# version1c.net
KiCad netlist of a schematic drawn in EAGLE
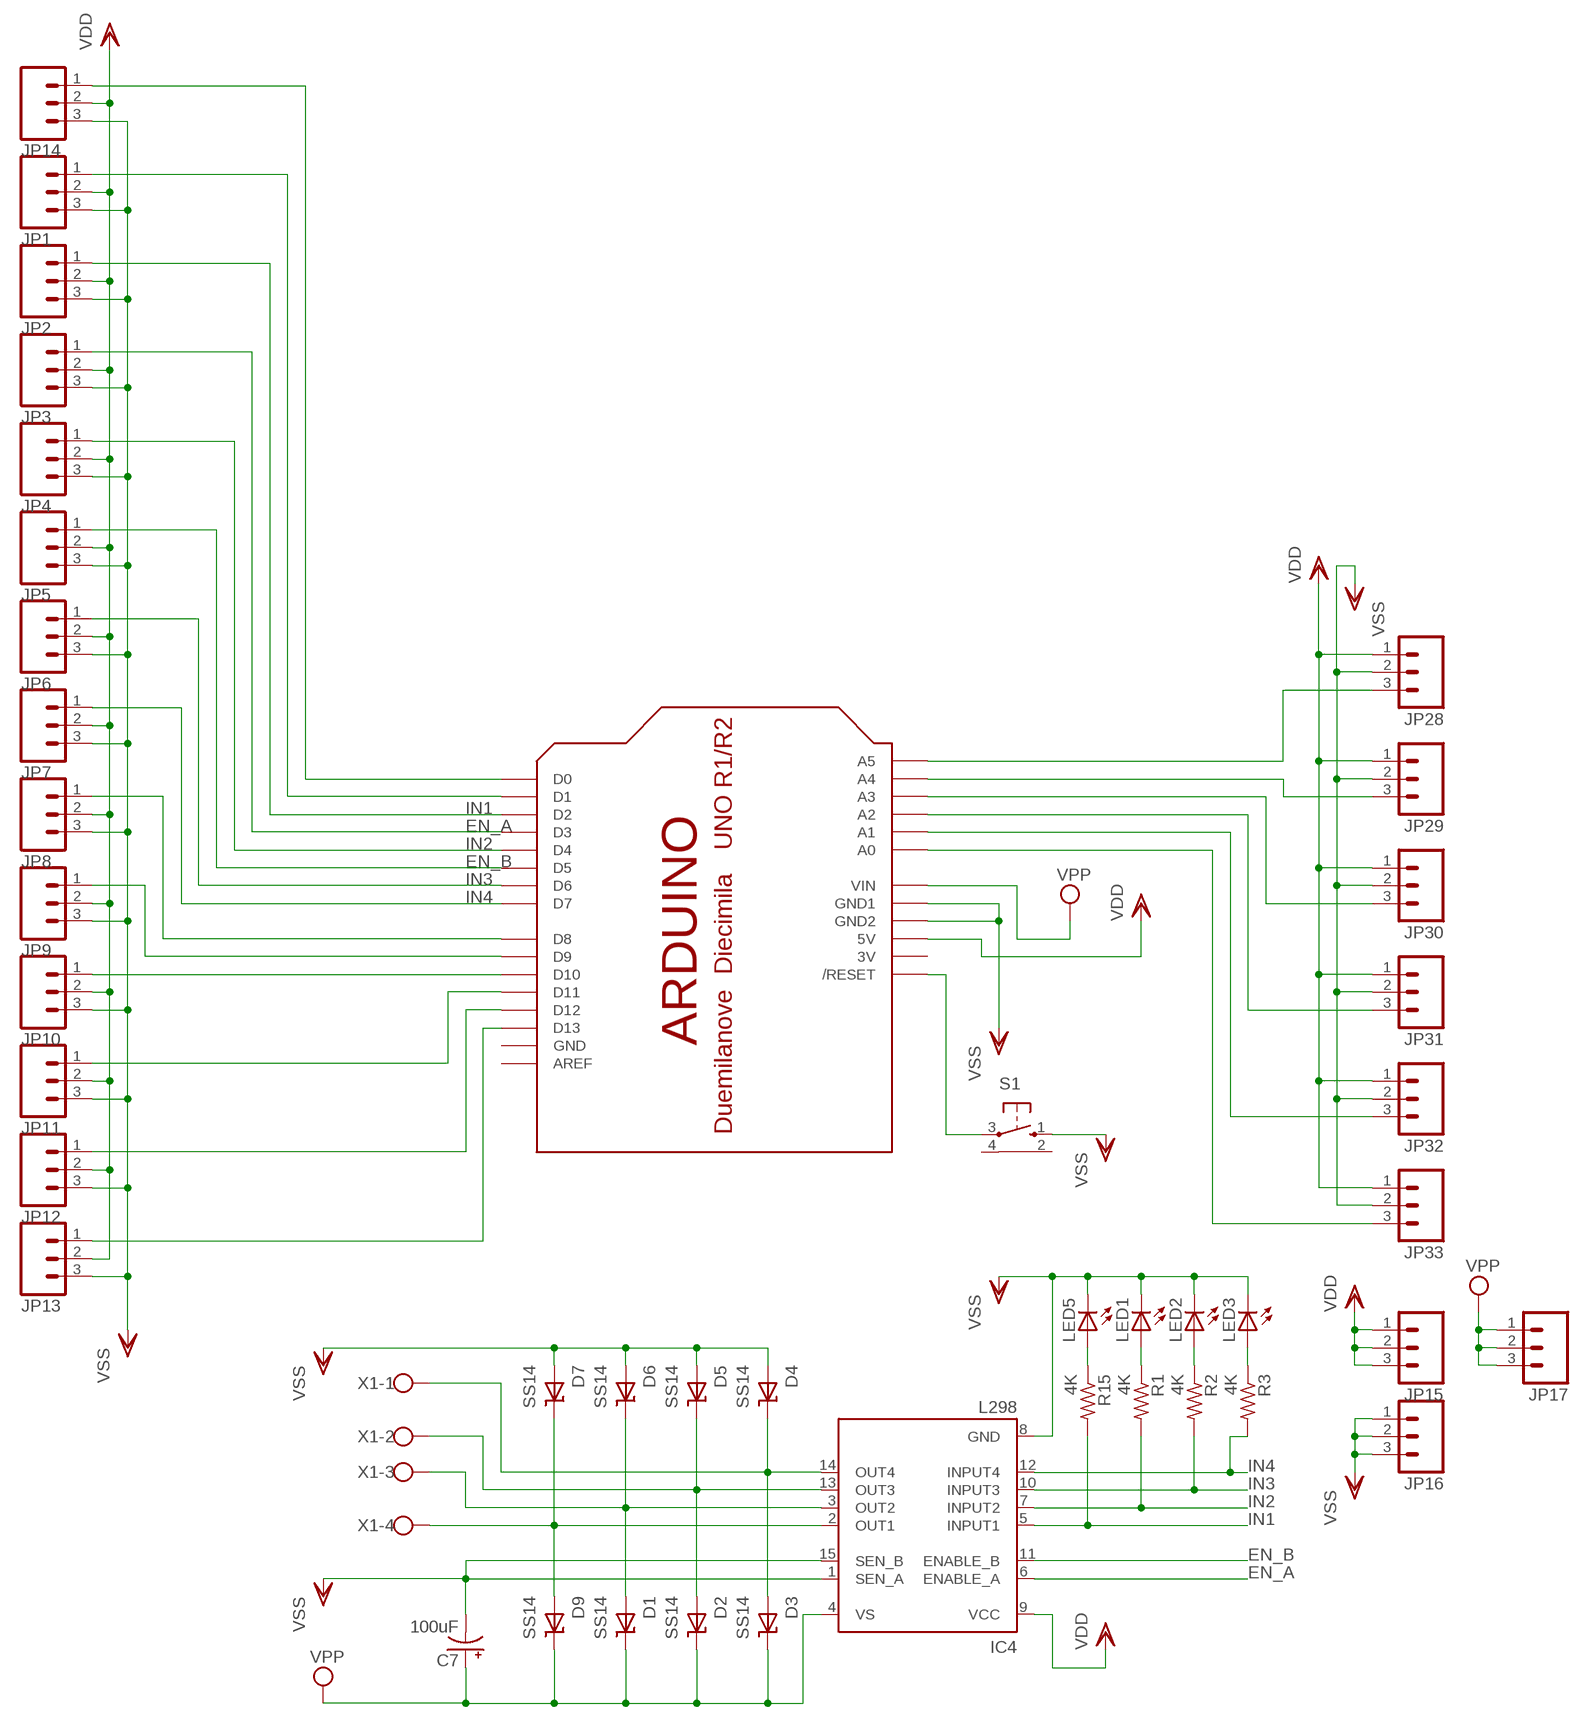
[diagram p0: schematic, sheet 1]

(export (version "E")
  (design (tool "Eeschema 10.0.6"))
  (components
    (comp (ref "C7")
      (value "100uF")
      (footprint "eagle-import:153CLV-0605")
      (libsource (lib "eagle-import") (part "CPOL-US153CLV-0605"))
    )
    (comp (ref "D1")
      (value "SS14")
      (footprint "eagle-import:SMA")
      (libsource (lib "eagle-import") (part "SS14"))
    )
    (comp (ref "D2")
      (value "SS14")
      (footprint "eagle-import:SMA")
      (libsource (lib "eagle-import") (part "SS14"))
    )
    (comp (ref "D3")
      (value "SS14")
      (footprint "eagle-import:SMA")
      (libsource (lib "eagle-import") (part "SS14"))
    )
    (comp (ref "D4")
      (value "SS14")
      (footprint "eagle-import:SMA")
      (libsource (lib "eagle-import") (part "SS14"))
    )
    (comp (ref "D5")
      (value "SS14")
      (footprint "eagle-import:SMA")
      (libsource (lib "eagle-import") (part "SS14"))
    )
    (comp (ref "D6")
      (value "SS14")
      (footprint "eagle-import:SMA")
      (libsource (lib "eagle-import") (part "SS14"))
    )
    (comp (ref "D7")
      (value "SS14")
      (footprint "eagle-import:SMA")
      (libsource (lib "eagle-import") (part "SS14"))
    )
    (comp (ref "D9")
      (value "SS14")
      (footprint "eagle-import:SMA")
      (libsource (lib "eagle-import") (part "SS14"))
    )
    (comp (ref "IC4")
      (value "L298")
      (footprint "eagle-import:MULTIWATT-15")
      (fields (field (name "MPN") "L298N"))
      (libsource (lib "eagle-import") (part "L298"))
    )
    (comp (ref "JP1")
      (value "M03PTH")
      (footprint "eagle-import:1X03")
      (libsource (lib "eagle-import") (part "M03PTH"))
    )
    (comp (ref "JP2")
      (value "M03PTH")
      (footprint "eagle-import:1X03")
      (libsource (lib "eagle-import") (part "M03PTH"))
    )
    (comp (ref "JP3")
      (value "M03PTH")
      (footprint "eagle-import:1X03")
      (libsource (lib "eagle-import") (part "M03PTH"))
    )
    (comp (ref "JP4")
      (value "M03PTH")
      (footprint "eagle-import:1X03")
      (libsource (lib "eagle-import") (part "M03PTH"))
    )
    (comp (ref "JP5")
      (value "M03PTH")
      (footprint "eagle-import:1X03")
      (libsource (lib "eagle-import") (part "M03PTH"))
    )
    (comp (ref "JP6")
      (value "M03PTH")
      (footprint "eagle-import:1X03")
      (libsource (lib "eagle-import") (part "M03PTH"))
    )
    (comp (ref "JP7")
      (value "M03PTH")
      (footprint "eagle-import:1X03")
      (libsource (lib "eagle-import") (part "M03PTH"))
    )
    (comp (ref "JP8")
      (value "M03PTH")
      (footprint "eagle-import:1X03")
      (libsource (lib "eagle-import") (part "M03PTH"))
    )
    (comp (ref "JP9")
      (value "M03PTH")
      (footprint "eagle-import:1X03")
      (libsource (lib "eagle-import") (part "M03PTH"))
    )
    (comp (ref "JP10")
      (value "M03PTH")
      (footprint "eagle-import:1X03")
      (libsource (lib "eagle-import") (part "M03PTH"))
    )
    (comp (ref "JP11")
      (value "M03PTH")
      (footprint "eagle-import:1X03")
      (libsource (lib "eagle-import") (part "M03PTH"))
    )
    (comp (ref "JP12")
      (value "M03PTH")
      (footprint "eagle-import:1X03")
      (libsource (lib "eagle-import") (part "M03PTH"))
    )
    (comp (ref "JP13")
      (value "M03PTH")
      (footprint "eagle-import:1X03")
      (libsource (lib "eagle-import") (part "M03PTH"))
    )
    (comp (ref "JP14")
      (value "M03PTH")
      (footprint "eagle-import:1X03")
      (libsource (lib "eagle-import") (part "M03PTH"))
    )
    (comp (ref "JP15")
      (value "M03PTH")
      (footprint "eagle-import:1X03")
      (libsource (lib "eagle-import") (part "M03PTH"))
    )
    (comp (ref "JP16")
      (value "M03PTH")
      (footprint "eagle-import:1X03")
      (libsource (lib "eagle-import") (part "M03PTH"))
    )
    (comp (ref "JP17")
      (value "M03PTH")
      (footprint "eagle-import:1X03")
      (libsource (lib "eagle-import") (part "M03PTH"))
    )
    (comp (ref "JP28")
      (value "M03PTH")
      (footprint "eagle-import:1X03")
      (libsource (lib "eagle-import") (part "M03PTH"))
    )
    (comp (ref "JP29")
      (value "M03PTH")
      (footprint "eagle-import:1X03")
      (libsource (lib "eagle-import") (part "M03PTH"))
    )
    (comp (ref "JP30")
      (value "M03PTH")
      (footprint "eagle-import:1X03")
      (libsource (lib "eagle-import") (part "M03PTH"))
    )
    (comp (ref "JP31")
      (value "M03PTH")
      (footprint "eagle-import:1X03")
      (libsource (lib "eagle-import") (part "M03PTH"))
    )
    (comp (ref "JP32")
      (value "M03PTH")
      (footprint "eagle-import:1X03")
      (libsource (lib "eagle-import") (part "M03PTH"))
    )
    (comp (ref "JP33")
      (value "M03PTH")
      (footprint "eagle-import:1X03")
      (libsource (lib "eagle-import") (part "M03PTH"))
    )
    (comp (ref "LED1")
      (value "LEDCHIP-LED0805")
      (footprint "eagle-import:CHIP-LED0805")
      (libsource (lib "eagle-import") (part "LEDCHIP-LED0805"))
    )
    (comp (ref "LED2")
      (value "LEDCHIP-LED0805")
      (footprint "eagle-import:CHIP-LED0805")
      (libsource (lib "eagle-import") (part "LEDCHIP-LED0805"))
    )
    (comp (ref "LED3")
      (value "LEDCHIP-LED0805")
      (footprint "eagle-import:CHIP-LED0805")
      (libsource (lib "eagle-import") (part "LEDCHIP-LED0805"))
    )
    (comp (ref "LED5")
      (value "LEDCHIP-LED0805")
      (footprint "eagle-import:CHIP-LED0805")
      (libsource (lib "eagle-import") (part "LEDCHIP-LED0805"))
    )
    (comp (ref "R1")
      (value "4K")
      (footprint "eagle-import:R0805")
      (libsource (lib "eagle-import") (part "R-US_R0805"))
    )
    (comp (ref "R2")
      (value "4K")
      (footprint "eagle-import:R0805")
      (libsource (lib "eagle-import") (part "R-US_R0805"))
    )
    (comp (ref "R3")
      (value "4K")
      (footprint "eagle-import:R0805")
      (libsource (lib "eagle-import") (part "R-US_R0805"))
    )
    (comp (ref "R15")
      (value "4K")
      (footprint "eagle-import:R0805")
      (libsource (lib "eagle-import") (part "R-US_R0805"))
    )
    (comp (ref "S1")
      (value "10-XX-RPAD")
      (footprint "eagle-import:B3F-10XX-RPAD")
      (libsource (lib "eagle-import") (part "10-XX-RPAD"))
    )
    (comp (ref "U$1")
      (value "ARDUINO-NOHOLE")
      (footprint "eagle-import:ARDUINO-NOHOLE")
      (libsource (lib "eagle-import") (part "ARDUINO-NOHOLE"))
    )
    (comp (ref "X1")
      (value "W237-4")
      (footprint "eagle-import:W237-4")
      (libsource (lib "eagle-import") (part "W237-4"))
    )
  )
  (nets
    (net (code "1") (name "/3V") (class "Default")
      (node (ref "U$1") (pin "3V") (pinfunction "3V_3V") (pintype "power_in"))
    )
    (net (code "2") (name "/EN_A") (class "Default")
      (node (ref "IC4") (pin "6") (pinfunction "ENABLE_A_6") (pintype "input"))
      (node (ref "JP3") (pin "1") (pinfunction "1_1") (pintype "passive"))
      (node (ref "U$1") (pin "D3") (pinfunction "D3_D3") (pintype "bidirectional"))
    )
    (net (code "3") (name "/EN_B") (class "Default")
      (node (ref "IC4") (pin "11") (pinfunction "ENABLE_B_11") (pintype "input"))
      (node (ref "JP5") (pin "1") (pinfunction "1_1") (pintype "passive"))
      (node (ref "U$1") (pin "D5") (pinfunction "D5_D5") (pintype "bidirectional"))
    )
    (net (code "4") (name "/GND") (class "Default")
      (node (ref "U$1") (pin "GND") (pinfunction "GND_GND") (pintype "power_in"))
    )
    (net (code "5") (name "/IN1") (class "Default")
      (node (ref "IC4") (pin "5") (pinfunction "INPUT1_5") (pintype "input"))
      (node (ref "JP2") (pin "1") (pinfunction "1_1") (pintype "passive"))
      (node (ref "R15") (pin "2") (pinfunction "2_2") (pintype "passive"))
      (node (ref "U$1") (pin "D2") (pinfunction "D2_D2") (pintype "bidirectional"))
    )
    (net (code "6") (name "/IN2") (class "Default")
      (node (ref "IC4") (pin "7") (pinfunction "INPUT2_7") (pintype "input"))
      (node (ref "JP4") (pin "1") (pinfunction "1_1") (pintype "passive"))
      (node (ref "R1") (pin "2") (pinfunction "2_2") (pintype "passive"))
      (node (ref "U$1") (pin "D4") (pinfunction "D4_D4") (pintype "bidirectional"))
    )
    (net (code "7") (name "/IN3") (class "Default")
      (node (ref "IC4") (pin "10") (pinfunction "INPUT3_10") (pintype "input"))
      (node (ref "JP6") (pin "1") (pinfunction "1_1") (pintype "passive"))
      (node (ref "R2") (pin "2") (pinfunction "2_2") (pintype "passive"))
      (node (ref "U$1") (pin "D6") (pinfunction "D6_D6") (pintype "bidirectional"))
    )
    (net (code "8") (name "/IN4") (class "Default")
      (node (ref "IC4") (pin "12") (pinfunction "INPUT4_12") (pintype "input"))
      (node (ref "JP7") (pin "1") (pinfunction "1_1") (pintype "passive"))
      (node (ref "R3") (pin "2") (pinfunction "2_2") (pintype "passive"))
      (node (ref "U$1") (pin "D7") (pinfunction "D7_D7") (pintype "bidirectional"))
    )
    (net (code "9") (name "Net-(D1-A)") (class "Default")
      (node (ref "D1") (pin "P$2") (pinfunction "A_P$2") (pintype "bidirectional"))
      (node (ref "D6") (pin "P$1") (pinfunction "K_P$1") (pintype "bidirectional"))
      (node (ref "IC4") (pin "3") (pinfunction "OUT2_3") (pintype "output"))
      (node (ref "X1") (pin "3") (pinfunction "KL_3") (pintype "passive"))
    )
    (net (code "10") (name "Net-(D2-A)") (class "Default")
      (node (ref "D2") (pin "P$2") (pinfunction "A_P$2") (pintype "bidirectional"))
      (node (ref "D5") (pin "P$1") (pinfunction "K_P$1") (pintype "bidirectional"))
      (node (ref "IC4") (pin "13") (pinfunction "OUT3_13") (pintype "output"))
      (node (ref "X1") (pin "2") (pinfunction "KL_2") (pintype "passive"))
    )
    (net (code "11") (name "Net-(D3-A)") (class "Default")
      (node (ref "D3") (pin "P$2") (pinfunction "A_P$2") (pintype "bidirectional"))
      (node (ref "D4") (pin "P$1") (pinfunction "K_P$1") (pintype "bidirectional"))
      (node (ref "IC4") (pin "14") (pinfunction "OUT4_14") (pintype "output"))
      (node (ref "X1") (pin "1") (pinfunction "KL_1") (pintype "passive"))
    )
    (net (code "12") (name "Net-(D7-K)") (class "Default")
      (node (ref "D7") (pin "P$1") (pinfunction "K_P$1") (pintype "bidirectional"))
      (node (ref "D9") (pin "P$2") (pinfunction "A_P$2") (pintype "bidirectional"))
      (node (ref "IC4") (pin "2") (pinfunction "OUT1_2") (pintype "output"))
      (node (ref "X1") (pin "4") (pinfunction "KL_4") (pintype "passive"))
    )
    (net (code "13") (name "Net-(JP1-Pad1)") (class "Default")
      (node (ref "JP1") (pin "1") (pinfunction "1_1") (pintype "passive"))
      (node (ref "U$1") (pin "D1") (pinfunction "D1_D1") (pintype "bidirectional"))
    )
    (net (code "14") (name "Net-(JP8-Pad1)") (class "Default")
      (node (ref "JP8") (pin "1") (pinfunction "1_1") (pintype "passive"))
      (node (ref "U$1") (pin "D8") (pinfunction "D8_D8") (pintype "bidirectional"))
    )
    (net (code "15") (name "Net-(JP9-Pad1)") (class "Default")
      (node (ref "JP9") (pin "1") (pinfunction "1_1") (pintype "passive"))
      (node (ref "U$1") (pin "D9") (pinfunction "D9_D9") (pintype "bidirectional"))
    )
    (net (code "16") (name "Net-(JP10-Pad1)") (class "Default")
      (node (ref "JP10") (pin "1") (pinfunction "1_1") (pintype "passive"))
      (node (ref "U$1") (pin "D10") (pinfunction "D10_D10") (pintype "bidirectional"))
    )
    (net (code "17") (name "Net-(JP11-Pad1)") (class "Default")
      (node (ref "JP11") (pin "1") (pinfunction "1_1") (pintype "passive"))
      (node (ref "U$1") (pin "D11") (pinfunction "D11_D11") (pintype "bidirectional"))
    )
    (net (code "18") (name "Net-(JP12-Pad1)") (class "Default")
      (node (ref "JP12") (pin "1") (pinfunction "1_1") (pintype "passive"))
      (node (ref "U$1") (pin "D12") (pinfunction "D12_D12") (pintype "bidirectional"))
    )
    (net (code "19") (name "Net-(JP13-Pad1)") (class "Default")
      (node (ref "JP13") (pin "1") (pinfunction "1_1") (pintype "passive"))
      (node (ref "U$1") (pin "D13") (pinfunction "D13_D13") (pintype "bidirectional"))
    )
    (net (code "20") (name "Net-(JP14-Pad1)") (class "Default")
      (node (ref "JP14") (pin "1") (pinfunction "1_1") (pintype "passive"))
      (node (ref "U$1") (pin "D0") (pinfunction "D0_D0") (pintype "bidirectional"))
    )
    (net (code "21") (name "Net-(JP28-Pad3)") (class "Default")
      (node (ref "JP28") (pin "3") (pinfunction "3_3") (pintype "passive"))
      (node (ref "U$1") (pin "A5") (pinfunction "A5_A5") (pintype "bidirectional"))
    )
    (net (code "22") (name "Net-(JP29-Pad3)") (class "Default")
      (node (ref "JP29") (pin "3") (pinfunction "3_3") (pintype "passive"))
      (node (ref "U$1") (pin "A4") (pinfunction "A4_A4") (pintype "bidirectional"))
    )
    (net (code "23") (name "Net-(JP30-Pad3)") (class "Default")
      (node (ref "JP30") (pin "3") (pinfunction "3_3") (pintype "passive"))
      (node (ref "U$1") (pin "A3") (pinfunction "A3_A3") (pintype "bidirectional"))
    )
    (net (code "24") (name "Net-(JP31-Pad3)") (class "Default")
      (node (ref "JP31") (pin "3") (pinfunction "3_3") (pintype "passive"))
      (node (ref "U$1") (pin "A2") (pinfunction "A2_A2") (pintype "bidirectional"))
    )
    (net (code "25") (name "Net-(JP32-Pad3)") (class "Default")
      (node (ref "JP32") (pin "3") (pinfunction "3_3") (pintype "passive"))
      (node (ref "U$1") (pin "A1") (pinfunction "A1_A1") (pintype "bidirectional"))
    )
    (net (code "26") (name "Net-(JP33-Pad3)") (class "Default")
      (node (ref "JP33") (pin "3") (pinfunction "3_3") (pintype "passive"))
      (node (ref "U$1") (pin "A0") (pinfunction "A0_A0") (pintype "bidirectional"))
    )
    (net (code "27") (name "Net-(LED1-PadA)") (class "Default")
      (node (ref "LED1") (pin "A") (pinfunction "A_A") (pintype "passive"))
      (node (ref "R1") (pin "1") (pinfunction "1_1") (pintype "passive"))
    )
    (net (code "28") (name "Net-(LED2-PadA)") (class "Default")
      (node (ref "LED2") (pin "A") (pinfunction "A_A") (pintype "passive"))
      (node (ref "R2") (pin "1") (pinfunction "1_1") (pintype "passive"))
    )
    (net (code "29") (name "Net-(LED3-PadA)") (class "Default")
      (node (ref "LED3") (pin "A") (pinfunction "A_A") (pintype "passive"))
      (node (ref "R3") (pin "1") (pinfunction "1_1") (pintype "passive"))
    )
    (net (code "30") (name "Net-(LED5-PadA)") (class "Default")
      (node (ref "LED5") (pin "A") (pinfunction "A_A") (pintype "passive"))
      (node (ref "R15") (pin "1") (pinfunction "1_1") (pintype "passive"))
    )
    (net (code "31") (name "Net-(S1-P)") (class "Default")
      (node (ref "S1") (pin "3") (pinfunction "P_3") (pintype "passive"))
      (node (ref "U$1") (pin "RESET") (pinfunction "/RESET_RESET") (pintype "bidirectional"))
    )
    (net (code "32") (name "VDD") (class "Default")
      (node (ref "IC4") (pin "9") (pinfunction "VCC_9") (pintype "power_in"))
      (node (ref "JP1") (pin "2") (pinfunction "2_2") (pintype "passive"))
      (node (ref "JP10") (pin "2") (pinfunction "2_2") (pintype "passive"))
      (node (ref "JP11") (pin "2") (pinfunction "2_2") (pintype "passive"))
      (node (ref "JP12") (pin "2") (pinfunction "2_2") (pintype "passive"))
      (node (ref "JP13") (pin "2") (pinfunction "2_2") (pintype "passive"))
      (node (ref "JP14") (pin "2") (pinfunction "2_2") (pintype "passive"))
      (node (ref "JP15") (pin "1") (pinfunction "1_1") (pintype "passive"))
      (node (ref "JP15") (pin "2") (pinfunction "2_2") (pintype "passive"))
      (node (ref "JP15") (pin "3") (pinfunction "3_3") (pintype "passive"))
      (node (ref "JP2") (pin "2") (pinfunction "2_2") (pintype "passive"))
      (node (ref "JP28") (pin "1") (pinfunction "1_1") (pintype "passive"))
      (node (ref "JP29") (pin "1") (pinfunction "1_1") (pintype "passive"))
      (node (ref "JP3") (pin "2") (pinfunction "2_2") (pintype "passive"))
      (node (ref "JP30") (pin "1") (pinfunction "1_1") (pintype "passive"))
      (node (ref "JP31") (pin "1") (pinfunction "1_1") (pintype "passive"))
      (node (ref "JP32") (pin "1") (pinfunction "1_1") (pintype "passive"))
      (node (ref "JP33") (pin "1") (pinfunction "1_1") (pintype "passive"))
      (node (ref "JP4") (pin "2") (pinfunction "2_2") (pintype "passive"))
      (node (ref "JP5") (pin "2") (pinfunction "2_2") (pintype "passive"))
      (node (ref "JP6") (pin "2") (pinfunction "2_2") (pintype "passive"))
      (node (ref "JP7") (pin "2") (pinfunction "2_2") (pintype "passive"))
      (node (ref "JP8") (pin "2") (pinfunction "2_2") (pintype "passive"))
      (node (ref "JP9") (pin "2") (pinfunction "2_2") (pintype "passive"))
      (node (ref "U$1") (pin "5V") (pinfunction "5V_5V") (pintype "power_in"))
    )
    (net (code "33") (name "VPP") (class "Default")
      (node (ref "C7") (pin "+") (pinfunction "+_+") (pintype "passive"))
      (node (ref "D1") (pin "P$1") (pinfunction "K_P$1") (pintype "bidirectional"))
      (node (ref "D2") (pin "P$1") (pinfunction "K_P$1") (pintype "bidirectional"))
      (node (ref "D3") (pin "P$1") (pinfunction "K_P$1") (pintype "bidirectional"))
      (node (ref "D9") (pin "P$1") (pinfunction "K_P$1") (pintype "bidirectional"))
      (node (ref "IC4") (pin "4") (pinfunction "VS_4") (pintype "power_in"))
      (node (ref "JP17") (pin "1") (pinfunction "1_1") (pintype "passive"))
      (node (ref "JP17") (pin "2") (pinfunction "2_2") (pintype "passive"))
      (node (ref "JP17") (pin "3") (pinfunction "3_3") (pintype "passive"))
      (node (ref "U$1") (pin "VIN") (pinfunction "VIN_VIN") (pintype "power_in"))
    )
    (net (code "34") (name "VSS") (class "Default")
      (node (ref "C7") (pin "-") (pinfunction "-_-") (pintype "passive"))
      (node (ref "D4") (pin "P$2") (pinfunction "A_P$2") (pintype "bidirectional"))
      (node (ref "D5") (pin "P$2") (pinfunction "A_P$2") (pintype "bidirectional"))
      (node (ref "D6") (pin "P$2") (pinfunction "A_P$2") (pintype "bidirectional"))
      (node (ref "D7") (pin "P$2") (pinfunction "A_P$2") (pintype "bidirectional"))
      (node (ref "IC4") (pin "1") (pinfunction "SEN_A_1") (pintype "input"))
      (node (ref "IC4") (pin "15") (pinfunction "SEN_B_15") (pintype "input"))
      (node (ref "IC4") (pin "8") (pinfunction "GND_8") (pintype "power_in"))
      (node (ref "JP1") (pin "3") (pinfunction "3_3") (pintype "passive"))
      (node (ref "JP10") (pin "3") (pinfunction "3_3") (pintype "passive"))
      (node (ref "JP11") (pin "3") (pinfunction "3_3") (pintype "passive"))
      (node (ref "JP12") (pin "3") (pinfunction "3_3") (pintype "passive"))
      (node (ref "JP13") (pin "3") (pinfunction "3_3") (pintype "passive"))
      (node (ref "JP14") (pin "3") (pinfunction "3_3") (pintype "passive"))
      (node (ref "JP16") (pin "1") (pinfunction "1_1") (pintype "passive"))
      (node (ref "JP16") (pin "2") (pinfunction "2_2") (pintype "passive"))
      (node (ref "JP16") (pin "3") (pinfunction "3_3") (pintype "passive"))
      (node (ref "JP2") (pin "3") (pinfunction "3_3") (pintype "passive"))
      (node (ref "JP28") (pin "2") (pinfunction "2_2") (pintype "passive"))
      (node (ref "JP29") (pin "2") (pinfunction "2_2") (pintype "passive"))
      (node (ref "JP3") (pin "3") (pinfunction "3_3") (pintype "passive"))
      (node (ref "JP30") (pin "2") (pinfunction "2_2") (pintype "passive"))
      (node (ref "JP31") (pin "2") (pinfunction "2_2") (pintype "passive"))
      (node (ref "JP32") (pin "2") (pinfunction "2_2") (pintype "passive"))
      (node (ref "JP33") (pin "2") (pinfunction "2_2") (pintype "passive"))
      (node (ref "JP4") (pin "3") (pinfunction "3_3") (pintype "passive"))
      (node (ref "JP5") (pin "3") (pinfunction "3_3") (pintype "passive"))
      (node (ref "JP6") (pin "3") (pinfunction "3_3") (pintype "passive"))
      (node (ref "JP7") (pin "3") (pinfunction "3_3") (pintype "passive"))
      (node (ref "JP8") (pin "3") (pinfunction "3_3") (pintype "passive"))
      (node (ref "JP9") (pin "3") (pinfunction "3_3") (pintype "passive"))
      (node (ref "LED1") (pin "C") (pinfunction "C_C") (pintype "passive"))
      (node (ref "LED2") (pin "C") (pinfunction "C_C") (pintype "passive"))
      (node (ref "LED3") (pin "C") (pinfunction "C_C") (pintype "passive"))
      (node (ref "LED5") (pin "C") (pinfunction "C_C") (pintype "passive"))
      (node (ref "S1") (pin "1") (pinfunction "S_1") (pintype "passive"))
      (node (ref "U$1") (pin "GND1") (pinfunction "GND1_GND1") (pintype "power_in"))
      (node (ref "U$1") (pin "GND2") (pinfunction "GND2_GND2") (pintype "power_in"))
    )
    (net (code "35") (name "unconnected-(S1-GND1-Pad2)") (class "Default")
      (node (ref "S1") (pin "2") (pinfunction "GND1_2") (pintype "passive"))
    )
    (net (code "36") (name "unconnected-(S1-GND2-Pad4)") (class "Default")
      (node (ref "S1") (pin "4") (pinfunction "GND2_4") (pintype "passive"))
    )
    (net (code "37") (name "unconnected-(U$1-PadAREF)") (class "Default")
      (node (ref "U$1") (pin "AREF") (pinfunction "AREF_AREF") (pintype "bidirectional"))
    )
  )
)
